# WCcircuit.net
KiCad netlist of a schematic drawn in Altium Designer
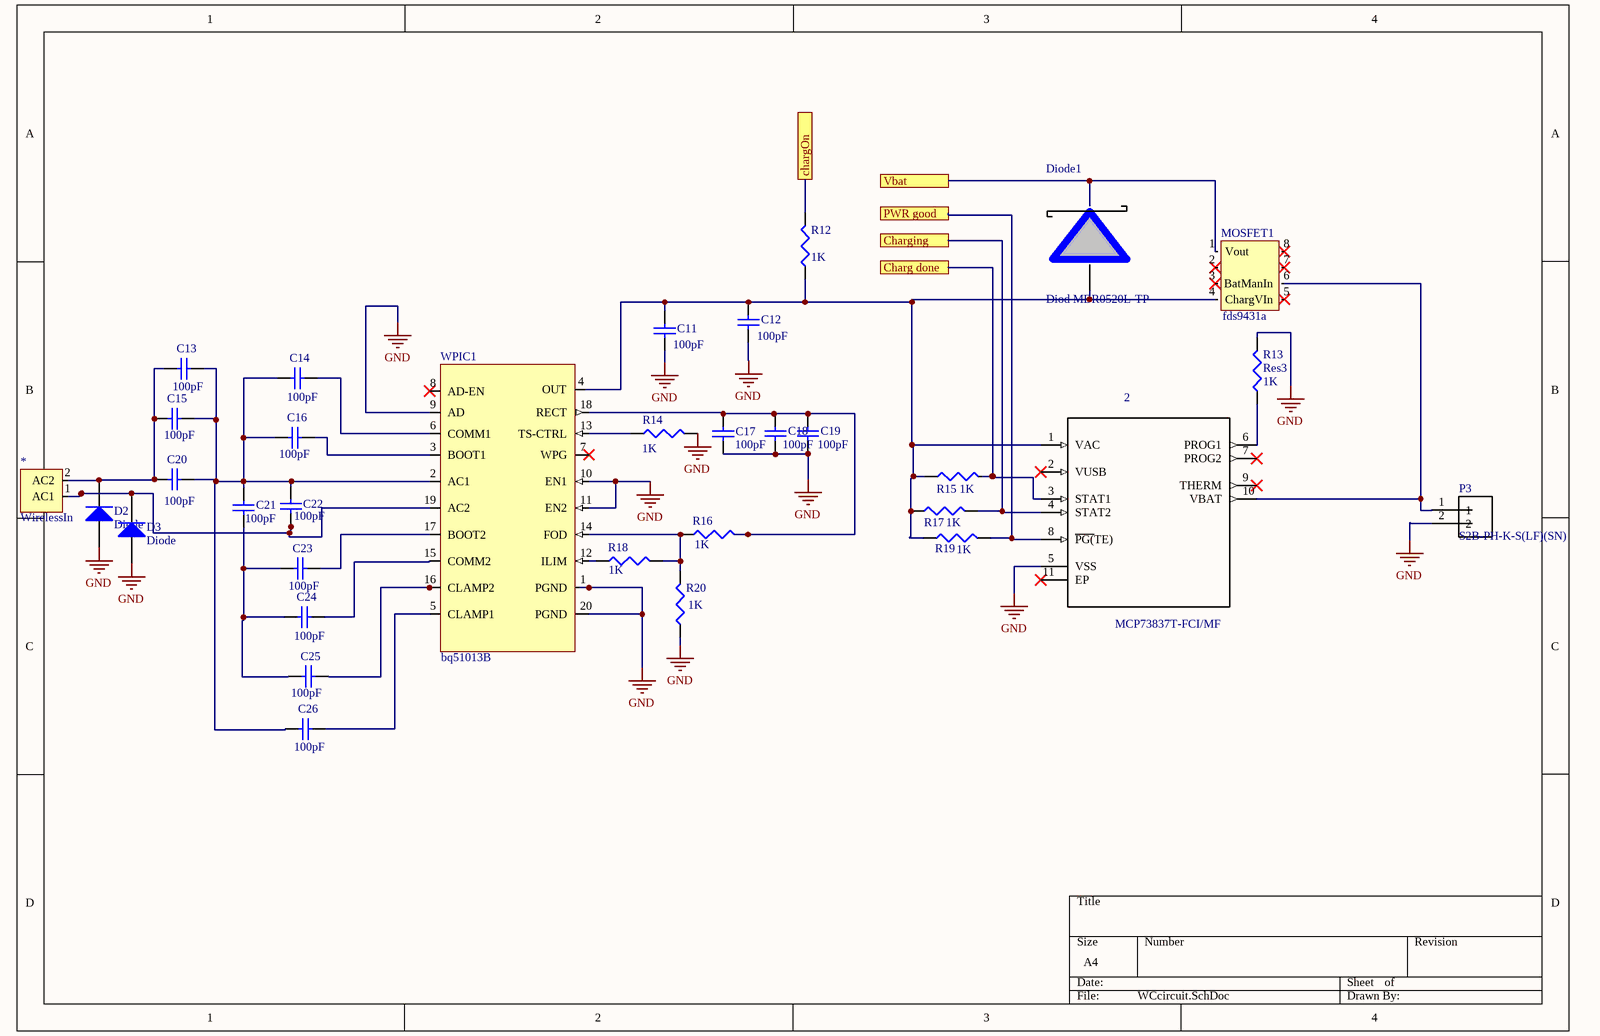
[diagram p0: WCcircuit.SchDoc]

(export (version "E")
  (design (tool "Eeschema 10.0.6"))
  (components
    (comp (ref "*")
      (value "WirelessIn")
      (footprint "WirelessIn")
      (libsource (lib "HGCDLibrary") (part "WirelessIn"))
    )
    (comp (ref "2")
      (value "MCP73837T-FCI/MF")
      (footprint "DFN300X300X100-11N")
      (description "MCP73837 Series 6 V Linear Battery Charge Controller Surface Mount - DFN-10")
      (fields (field (name "MF") "Microchip"))
      (libsource (lib "HGCDLibrary") (part "MCP73837T-FCI/MF"))
    )
    (comp (ref "C11")
      (value "100pF")
      (footprint "C1206")
      (description "Capacitor (Semiconductor SIM Model)")
      (fields (field (name "Comment") "Cap Semi") (field (name "PUBLISHER") "Altium Limited"))
      (libsource (lib "Miscellaneous Devices") (part "Cap Semi"))
    )
    (comp (ref "C12")
      (value "100pF")
      (footprint "C1206")
      (description "Capacitor (Semiconductor SIM Model)")
      (fields (field (name "Comment") "Cap Semi") (field (name "PUBLISHER") "Altium Limited"))
      (libsource (lib "Miscellaneous Devices") (part "Cap Semi"))
    )
    (comp (ref "C13")
      (value "100pF")
      (footprint "C1206")
      (description "Capacitor (Semiconductor SIM Model)")
      (fields (field (name "Comment") "Cap Semi") (field (name "PUBLISHER") "Altium Limited"))
      (libsource (lib "Miscellaneous Devices") (part "Cap Semi"))
    )
    (comp (ref "C14")
      (value "100pF")
      (footprint "C1206")
      (description "Capacitor (Semiconductor SIM Model)")
      (fields (field (name "Comment") "Cap Semi") (field (name "PUBLISHER") "Altium Limited"))
      (libsource (lib "Miscellaneous Devices") (part "Cap Semi"))
    )
    (comp (ref "C15")
      (value "100pF")
      (footprint "C1206")
      (description "Capacitor (Semiconductor SIM Model)")
      (fields (field (name "Comment") "Cap Semi") (field (name "PUBLISHER") "Altium Limited"))
      (libsource (lib "Miscellaneous Devices") (part "Cap Semi"))
    )
    (comp (ref "C16")
      (value "100pF")
      (footprint "C1206")
      (description "Capacitor (Semiconductor SIM Model)")
      (fields (field (name "Comment") "Cap Semi") (field (name "PUBLISHER") "Altium Limited"))
      (libsource (lib "Miscellaneous Devices") (part "Cap Semi"))
    )
    (comp (ref "C17")
      (value "100pF")
      (footprint "C1206")
      (description "Capacitor (Semiconductor SIM Model)")
      (fields (field (name "Comment") "Cap Semi") (field (name "PUBLISHER") "Altium Limited"))
      (libsource (lib "Miscellaneous Devices") (part "Cap Semi"))
    )
    (comp (ref "C18")
      (value "100pF")
      (footprint "C1206")
      (description "Capacitor (Semiconductor SIM Model)")
      (fields (field (name "Comment") "Cap Semi") (field (name "PUBLISHER") "Altium Limited"))
      (libsource (lib "Miscellaneous Devices") (part "Cap Semi"))
    )
    (comp (ref "C19")
      (value "100pF")
      (footprint "C1206")
      (description "Capacitor (Semiconductor SIM Model)")
      (fields (field (name "Comment") "Cap Semi") (field (name "PUBLISHER") "Altium Limited"))
      (libsource (lib "Miscellaneous Devices") (part "Cap Semi"))
    )
    (comp (ref "C20")
      (value "100pF")
      (footprint "C1206")
      (description "Capacitor (Semiconductor SIM Model)")
      (fields (field (name "Comment") "Cap Semi") (field (name "PUBLISHER") "Altium Limited"))
      (libsource (lib "Miscellaneous Devices") (part "Cap Semi"))
    )
    (comp (ref "C21")
      (value "100pF")
      (footprint "C1206")
      (description "Capacitor (Semiconductor SIM Model)")
      (fields (field (name "Comment") "Cap Semi") (field (name "PUBLISHER") "Altium Limited"))
      (libsource (lib "Miscellaneous Devices") (part "Cap Semi"))
    )
    (comp (ref "C22")
      (value "100pF")
      (footprint "C1206")
      (description "Capacitor (Semiconductor SIM Model)")
      (fields (field (name "Comment") "Cap Semi") (field (name "PUBLISHER") "Altium Limited"))
      (libsource (lib "Miscellaneous Devices") (part "Cap Semi"))
    )
    (comp (ref "C23")
      (value "100pF")
      (footprint "C1206")
      (description "Capacitor (Semiconductor SIM Model)")
      (fields (field (name "Comment") "Cap Semi") (field (name "PUBLISHER") "Altium Limited"))
      (libsource (lib "Miscellaneous Devices") (part "Cap Semi"))
    )
    (comp (ref "C24")
      (value "100pF")
      (footprint "C1206")
      (description "Capacitor (Semiconductor SIM Model)")
      (fields (field (name "Comment") "Cap Semi") (field (name "PUBLISHER") "Altium Limited"))
      (libsource (lib "Miscellaneous Devices") (part "Cap Semi"))
    )
    (comp (ref "C25")
      (value "100pF")
      (footprint "C1206")
      (description "Capacitor (Semiconductor SIM Model)")
      (fields (field (name "Comment") "Cap Semi") (field (name "PUBLISHER") "Altium Limited"))
      (libsource (lib "Miscellaneous Devices") (part "Cap Semi"))
    )
    (comp (ref "C26")
      (value "100pF")
      (footprint "C1206")
      (description "Capacitor (Semiconductor SIM Model)")
      (fields (field (name "Comment") "Cap Semi") (field (name "PUBLISHER") "Altium Limited"))
      (libsource (lib "Miscellaneous Devices") (part "Cap Semi"))
    )
    (comp (ref "D2")
      (value "Diode")
      (footprint "SMC")
      (description "Default Diode")
      (fields (field (name "PUBLISHER") "Altium Limited"))
      (libsource (lib "Miscellaneous Devices") (part "Diode"))
    )
    (comp (ref "D3")
      (value "Diode")
      (footprint "SMC")
      (description "Default Diode")
      (fields (field (name "PUBLISHER") "Altium Limited"))
      (libsource (lib "Miscellaneous Devices") (part "Diode"))
    )
    (comp (ref "Diode1")
      (value "Diod MBR0520L-TP")
      (footprint "SOD3716X135N")
      (libsource (lib "HGCDLibrary") (part "Diod MBR0520L-TP"))
    )
    (comp (ref "MOSFET1")
      (value "fds9431a")
      (footprint "SOIC127P600X175-8N")
      (libsource (lib "HGCDLibrary") (part "fds9431a"))
    )
    (comp (ref "P3")
      (value "S2B-PH-K-S(LF)(SN)")
      (footprint "JST_S2B-PH-K-S(LF)(SN)")
      (description "Header Side Entry 2way")
      (fields (field (name "MP") "S2B-PH-K-S (LF)(SN)") (field (name "MF") "JST"))
      (libsource (lib "HGCDLibrary") (part "S2B-PH-K-S(LF)(SN)"))
    )
    (comp (ref "R12")
      (value "1K")
      (footprint "J1-0603")
      (description "Resistor")
      (fields (field (name "Comment") "Res3") (field (name "PUBLISHER") "Altium Limited"))
      (libsource (lib "Miscellaneous Devices") (part "Res3"))
    )
    (comp (ref "R13")
      (value "Res3")
      (footprint "J1-0603")
      (description "Resistor")
      (fields (field (name "ALTIUM_VALUE") "1K") (field (name "PUBLISHER") "Altium Limited"))
      (libsource (lib "Miscellaneous Devices") (part "Res3"))
    )
    (comp (ref "R14")
      (value "1K")
      (footprint "J1-0603")
      (description "Resistor")
      (fields (field (name "Comment") "Res3") (field (name "PUBLISHER") "Altium Limited"))
      (libsource (lib "Miscellaneous Devices") (part "Res3"))
    )
    (comp (ref "R15")
      (value "1K")
      (footprint "J1-0603")
      (description "Resistor")
      (fields (field (name "Comment") "Res3") (field (name "PUBLISHER") "Altium Limited"))
      (libsource (lib "Miscellaneous Devices") (part "Res3"))
    )
    (comp (ref "R16")
      (value "1K")
      (footprint "J1-0603")
      (description "Resistor")
      (fields (field (name "Comment") "Res3") (field (name "PUBLISHER") "Altium Limited"))
      (libsource (lib "Miscellaneous Devices") (part "Res3"))
    )
    (comp (ref "R17")
      (value "1K")
      (footprint "J1-0603")
      (description "Resistor")
      (fields (field (name "Comment") "Res3") (field (name "PUBLISHER") "Altium Limited"))
      (libsource (lib "Miscellaneous Devices") (part "Res3"))
    )
    (comp (ref "R18")
      (value "1K")
      (footprint "J1-0603")
      (description "Resistor")
      (fields (field (name "Comment") "Res3") (field (name "PUBLISHER") "Altium Limited"))
      (libsource (lib "Miscellaneous Devices") (part "Res3"))
    )
    (comp (ref "R19")
      (value "1K")
      (footprint "J1-0603")
      (description "Resistor")
      (fields (field (name "Comment") "Res3") (field (name "PUBLISHER") "Altium Limited"))
      (libsource (lib "Miscellaneous Devices") (part "Res3"))
    )
    (comp (ref "R20")
      (value "1K")
      (footprint "J1-0603")
      (description "Resistor")
      (fields (field (name "Comment") "Res3") (field (name "PUBLISHER") "Altium Limited"))
      (libsource (lib "Miscellaneous Devices") (part "Res3"))
    )
    (comp (ref "WPIC1")
      (value "bq51013B")
      (footprint "CONTROLLER_MSP430FR2522IRHLT")
      (libsource (lib "HGCDLibrary") (part "bq51013B"))
    )
  )
  (nets
    (net (code "1") (name "/Charg done") (class "Default")
      (node (ref "2") (pin "3") (pinfunction "STAT1_3") (pintype "input"))
      (node (ref "R15") (pin "2") (pinfunction "2_2") (pintype "passive"))
    )
    (net (code "2") (name "/Charging") (class "Default")
      (node (ref "2") (pin "4") (pinfunction "STAT2_4") (pintype "input"))
      (node (ref "R17") (pin "2") (pinfunction "2_2") (pintype "passive"))
    )
    (net (code "3") (name "/PWR good") (class "Default")
      (node (ref "2") (pin "8") (pinfunction "~{PG(}TE)_8") (pintype "input"))
      (node (ref "R19") (pin "2") (pinfunction "2_2") (pintype "passive"))
    )
    (net (code "4") (name "/Vbat") (class "Default")
      (node (ref "Diode1") (pin "C") (pinfunction "26_C") (pintype "passive"))
      (node (ref "MOSFET1") (pin "1") (pinfunction "Vout_1") (pintype "output"))
    )
    (net (code "5") (name "/chargOn") (class "Default")
      (node (ref "R12") (pin "2") (pinfunction "2_2") (pintype "passive"))
    )
    (net (code "6") (name "GND") (class "Default")
      (node (ref "2") (pin "5") (pinfunction "VSS_5") (pintype "power_in"))
      (node (ref "C11") (pin "1") (pinfunction "1_1") (pintype "passive"))
      (node (ref "C12") (pin "1") (pinfunction "1_1") (pintype "passive"))
      (node (ref "C17") (pin "1") (pinfunction "1_1") (pintype "passive"))
      (node (ref "C18") (pin "1") (pinfunction "1_1") (pintype "passive"))
      (node (ref "C19") (pin "1") (pinfunction "1_1") (pintype "passive"))
      (node (ref "D2") (pin "1") (pinfunction "A_1") (pintype "passive"))
      (node (ref "D3") (pin "1") (pinfunction "A_1") (pintype "passive"))
      (node (ref "P3") (pin "2") (pinfunction "2_2") (pintype "passive"))
      (node (ref "R13") (pin "2") (pinfunction "2_2") (pintype "passive"))
      (node (ref "R14") (pin "2") (pinfunction "2_2") (pintype "passive"))
      (node (ref "R20") (pin "1") (pinfunction "1_1") (pintype "passive"))
      (node (ref "WPIC1") (pin "1") (pinfunction "PGND_1") (pintype "power_in"))
      (node (ref "WPIC1") (pin "10") (pinfunction "EN1_10") (pintype "input"))
      (node (ref "WPIC1") (pin "11") (pinfunction "EN2_11") (pintype "input"))
      (node (ref "WPIC1") (pin "20") (pinfunction "PGND_20") (pintype "power_in"))
      (node (ref "WPIC1") (pin "9") (pinfunction "AD_9") (pintype "power_in"))
    )
    (net (code "7") (name "Net-(*-AC1)") (class "Default")
      (node (ref "*") (pin "1") (pinfunction "AC1_1") (pintype "passive"))
      (node (ref "C22") (pin "1") (pinfunction "1_1") (pintype "passive"))
      (node (ref "D3") (pin "2") (pinfunction "K_2") (pintype "passive"))
      (node (ref "WPIC1") (pin "19") (pinfunction "AC2_19") (pintype "input"))
    )
    (net (code "8") (name "Net-(*-AC2)") (class "Default")
      (node (ref "*") (pin "2") (pinfunction "AC2_2") (pintype "passive"))
      (node (ref "C13") (pin "1") (pinfunction "1_1") (pintype "passive"))
      (node (ref "C15") (pin "1") (pinfunction "1_1") (pintype "passive"))
      (node (ref "C20") (pin "1") (pinfunction "1_1") (pintype "passive"))
      (node (ref "D2") (pin "2") (pinfunction "K_2") (pintype "passive"))
    )
    (net (code "9") (name "Net-(2-PROG1)") (class "Default")
      (node (ref "2") (pin "6") (pinfunction "PROG1_6") (pintype "output"))
      (node (ref "R13") (pin "1") (pinfunction "1_1") (pintype "passive"))
    )
    (net (code "10") (name "Net-(2-VAC)") (class "Default")
      (node (ref "2") (pin "1") (pinfunction "VAC_1") (pintype "input"))
      (node (ref "C11") (pin "2") (pinfunction "2_2") (pintype "passive"))
      (node (ref "C12") (pin "2") (pinfunction "2_2") (pintype "passive"))
      (node (ref "Diode1") (pin "A") (pinfunction "26_A") (pintype "passive"))
      (node (ref "MOSFET1") (pin "4") (pinfunction "ChargVIn_4") (pintype "input"))
      (node (ref "R12") (pin "1") (pinfunction "1_1") (pintype "passive"))
      (node (ref "R15") (pin "1") (pinfunction "1_1") (pintype "passive"))
      (node (ref "R17") (pin "1") (pinfunction "1_1") (pintype "passive"))
      (node (ref "R19") (pin "1") (pinfunction "1_1") (pintype "passive"))
      (node (ref "WPIC1") (pin "4") (pinfunction "OUT_4") (pintype "power_in"))
    )
    (net (code "11") (name "Net-(2-VBAT)") (class "Default")
      (node (ref "2") (pin "10") (pinfunction "VBAT_10") (pintype "output"))
      (node (ref "MOSFET1") (pin "6") (pinfunction "BatManIn_6") (pintype "input"))
      (node (ref "P3") (pin "1") (pinfunction "1_1") (pintype "passive"))
    )
    (net (code "12") (name "Net-(C21-Pad1)") (class "Default")
      (node (ref "C21") (pin "1") (pinfunction "1_1") (pintype "passive"))
      (node (ref "C23") (pin "1") (pinfunction "1_1") (pintype "passive"))
      (node (ref "C24") (pin "1") (pinfunction "1_1") (pintype "passive"))
      (node (ref "C25") (pin "1") (pinfunction "1_1") (pintype "passive"))
    )
    (net (code "13") (name "Net-(WPIC1-AC1)") (class "Default")
      (node (ref "C13") (pin "2") (pinfunction "2_2") (pintype "passive"))
      (node (ref "C14") (pin "1") (pinfunction "1_1") (pintype "passive"))
      (node (ref "C15") (pin "2") (pinfunction "2_2") (pintype "passive"))
      (node (ref "C16") (pin "1") (pinfunction "1_1") (pintype "passive"))
      (node (ref "C20") (pin "2") (pinfunction "2_2") (pintype "passive"))
      (node (ref "C21") (pin "2") (pinfunction "2_2") (pintype "passive"))
      (node (ref "C22") (pin "2") (pinfunction "2_2") (pintype "passive"))
      (node (ref "C26") (pin "1") (pinfunction "1_1") (pintype "passive"))
      (node (ref "WPIC1") (pin "2") (pinfunction "AC1_2") (pintype "input"))
    )
    (net (code "14") (name "Net-(WPIC1-BOOT1)") (class "Default")
      (node (ref "C16") (pin "2") (pinfunction "2_2") (pintype "passive"))
      (node (ref "WPIC1") (pin "3") (pinfunction "BOOT1_3") (pintype "output"))
    )
    (net (code "15") (name "Net-(WPIC1-BOOT2)") (class "Default")
      (node (ref "C23") (pin "2") (pinfunction "2_2") (pintype "passive"))
      (node (ref "WPIC1") (pin "17") (pinfunction "BOOT2_17") (pintype "output"))
    )
    (net (code "16") (name "Net-(WPIC1-CLAMP1)") (class "Default")
      (node (ref "C26") (pin "2") (pinfunction "2_2") (pintype "passive"))
      (node (ref "WPIC1") (pin "5") (pinfunction "CLAMP1_5") (pintype "output"))
    )
    (net (code "17") (name "Net-(WPIC1-CLAMP2)") (class "Default")
      (node (ref "C25") (pin "2") (pinfunction "2_2") (pintype "passive"))
      (node (ref "WPIC1") (pin "16") (pinfunction "CLAMP2_16") (pintype "output"))
    )
    (net (code "18") (name "Net-(WPIC1-COMM1)") (class "Default")
      (node (ref "C14") (pin "2") (pinfunction "2_2") (pintype "passive"))
      (node (ref "WPIC1") (pin "6") (pinfunction "COMM1_6") (pintype "output"))
    )
    (net (code "19") (name "Net-(WPIC1-COMM2)") (class "Default")
      (node (ref "C24") (pin "2") (pinfunction "2_2") (pintype "passive"))
      (node (ref "WPIC1") (pin "15") (pinfunction "COMM2_15") (pintype "output"))
    )
    (net (code "20") (name "Net-(WPIC1-FOD)") (class "Default")
      (node (ref "R16") (pin "1") (pinfunction "1_1") (pintype "passive"))
      (node (ref "R18") (pin "2") (pinfunction "2_2") (pintype "passive"))
      (node (ref "R20") (pin "2") (pinfunction "2_2") (pintype "passive"))
      (node (ref "WPIC1") (pin "14") (pinfunction "FOD_14") (pintype "input"))
    )
    (net (code "21") (name "Net-(WPIC1-ILIM)") (class "Default")
      (node (ref "R18") (pin "1") (pinfunction "1_1") (pintype "passive"))
      (node (ref "WPIC1") (pin "12") (pinfunction "ILIM_12") (pintype "input"))
    )
    (net (code "22") (name "Net-(WPIC1-RECT)") (class "Default")
      (node (ref "C17") (pin "2") (pinfunction "2_2") (pintype "passive"))
      (node (ref "C18") (pin "2") (pinfunction "2_2") (pintype "passive"))
      (node (ref "C19") (pin "2") (pinfunction "2_2") (pintype "passive"))
      (node (ref "R16") (pin "2") (pinfunction "2_2") (pintype "passive"))
      (node (ref "WPIC1") (pin "18") (pinfunction "RECT_18") (pintype "output"))
    )
    (net (code "23") (name "Net-(WPIC1-TS-CTRL)") (class "Default")
      (node (ref "R14") (pin "1") (pinfunction "1_1") (pintype "passive"))
      (node (ref "WPIC1") (pin "13") (pinfunction "TS-CTRL_13") (pintype "input"))
    )
    (net (code "24") (name "unconnected-(2-EP-Pad11)") (class "Default")
      (node (ref "2") (pin "11") (pinfunction "EP_11") (pintype "passive+no_connect"))
    )
    (net (code "25") (name "unconnected-(2-PROG2-Pad7)") (class "Default")
      (node (ref "2") (pin "7") (pinfunction "PROG2_7") (pintype "output+no_connect"))
    )
    (net (code "26") (name "unconnected-(2-THERM-Pad9)") (class "Default")
      (node (ref "2") (pin "9") (pinfunction "THERM_9") (pintype "output+no_connect"))
    )
    (net (code "27") (name "unconnected-(2-VUSB-Pad2)") (class "Default")
      (node (ref "2") (pin "2") (pinfunction "VUSB_2") (pintype "input+no_connect"))
    )
    (net (code "28") (name "unconnected-(MOSFET1-22-Pad2)") (class "Default")
      (node (ref "MOSFET1") (pin "2") (pinfunction "22_2") (pintype "passive+no_connect"))
    )
    (net (code "29") (name "unconnected-(MOSFET1-22-Pad5)") (class "Default")
      (node (ref "MOSFET1") (pin "5") (pinfunction "22_5") (pintype "passive+no_connect"))
    )
    (net (code "30") (name "unconnected-(MOSFET1-22-Pad7)") (class "Default")
      (node (ref "MOSFET1") (pin "7") (pinfunction "22_7") (pintype "passive+no_connect"))
    )
    (net (code "31") (name "unconnected-(MOSFET1-22-Pad8)") (class "Default")
      (node (ref "MOSFET1") (pin "8") (pinfunction "22_8") (pintype "passive+no_connect"))
    )
    (net (code "32") (name "unconnected-(MOSFET1-23-Pad3)") (class "Default")
      (node (ref "MOSFET1") (pin "3") (pinfunction "23_3") (pintype "passive+no_connect"))
    )
    (net (code "33") (name "unconnected-(WPIC1-AD-EN-Pad8)") (class "Default")
      (node (ref "WPIC1") (pin "8") (pinfunction "AD-EN_8") (pintype "power_in+no_connect"))
    )
    (net (code "34") (name "unconnected-(WPIC1-WPG-Pad7)") (class "Default")
      (node (ref "WPIC1") (pin "7") (pinfunction "WPG_7") (pintype "power_in+no_connect"))
    )
  )
)
